# Main.net
KiCad netlist of a schematic drawn in Altium Designer
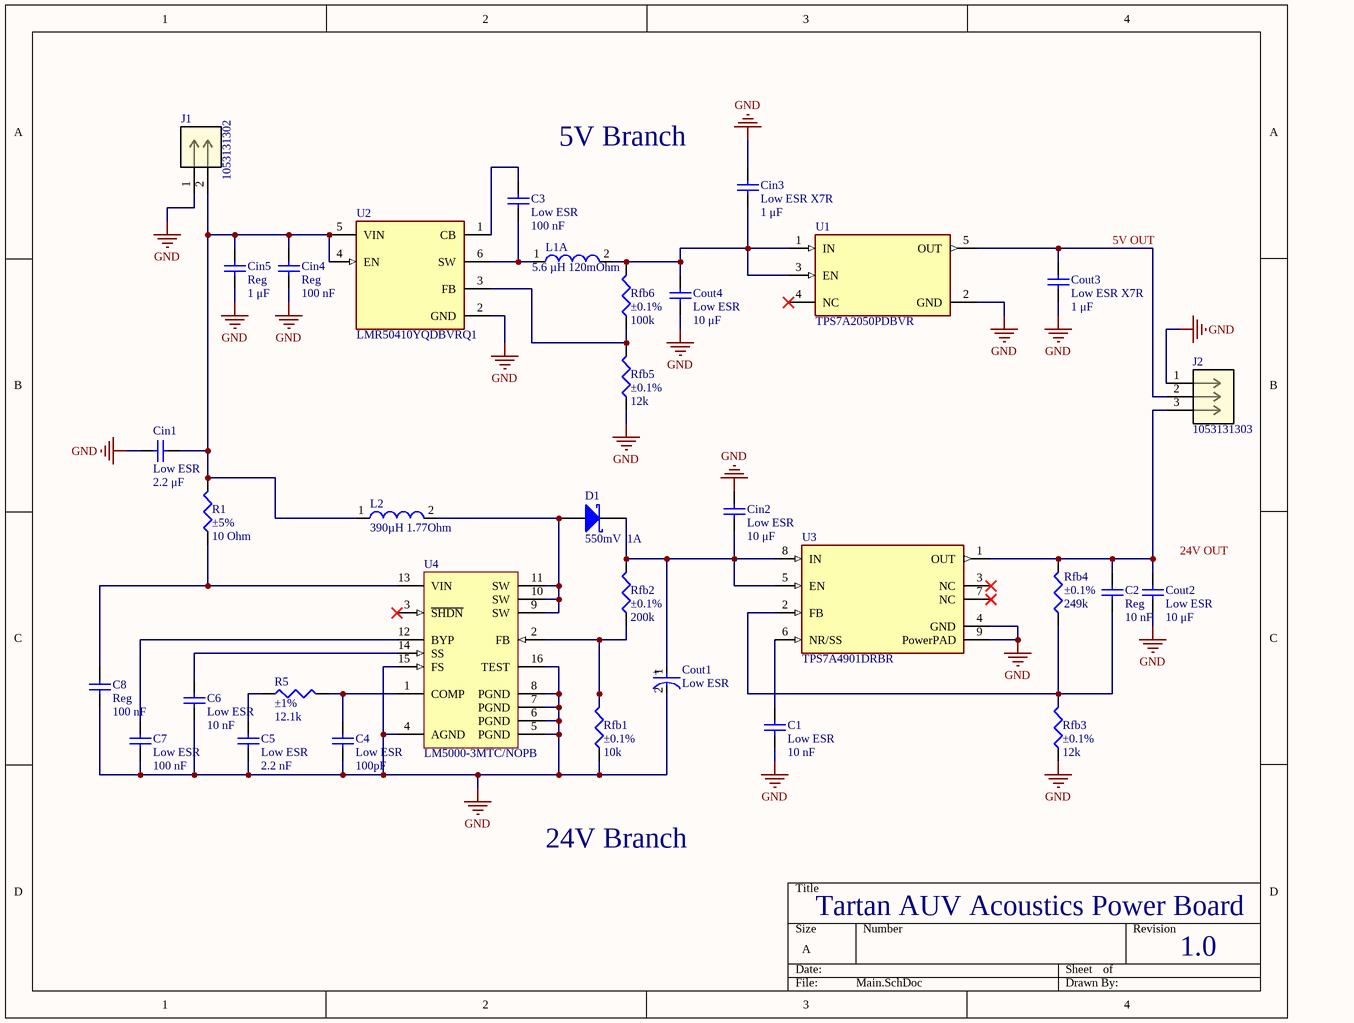
[diagram p0: Main.SchDoc]

(export (version "E")
  (design (tool "Eeschema 10.0.6"))
  (components
    (comp (ref "C1")
      (value "Low ESR")
      (footprint "C0805")
      (description "Capacitor")
      (fields (field (name "ALTIUM_VALUE") "10 nF") (field (name "PUBLISHER") "Altium Limited"))
      (libsource (lib "Miscellaneous Devices") (part "Cap"))
    )
    (comp (ref "C2")
      (value "Reg")
      (footprint "C0805")
      (description "Capacitor")
      (fields (field (name "ALTIUM_VALUE") "10 nF") (field (name "PUBLISHER") "Altium Limited"))
      (libsource (lib "Miscellaneous Devices") (part "Cap"))
    )
    (comp (ref "C3")
      (value "Low ESR")
      (footprint "C0805")
      (description "Capacitor")
      (fields (field (name "ALTIUM_VALUE") "100 nF") (field (name "PUBLISHER") "Altium Limited"))
      (libsource (lib "Miscellaneous Devices") (part "Cap"))
    )
    (comp (ref "C4")
      (value "Low ESR")
      (footprint "C0805")
      (description "Capacitor")
      (fields (field (name "ALTIUM_VALUE") "100pF") (field (name "PUBLISHER") "Altium Limited"))
      (libsource (lib "Miscellaneous Devices") (part "Cap"))
    )
    (comp (ref "C5")
      (value "Low ESR")
      (footprint "C0805")
      (description "Capacitor")
      (fields (field (name "ALTIUM_VALUE") "2.2 nF") (field (name "PUBLISHER") "Altium Limited"))
      (libsource (lib "Miscellaneous Devices") (part "Cap"))
    )
    (comp (ref "C6")
      (value "Low ESR")
      (footprint "C0805")
      (description "Capacitor")
      (fields (field (name "ALTIUM_VALUE") "10 nF") (field (name "PUBLISHER") "Altium Limited"))
      (libsource (lib "Miscellaneous Devices") (part "Cap"))
    )
    (comp (ref "C7")
      (value "Low ESR")
      (footprint "C0805")
      (description "Capacitor")
      (fields (field (name "ALTIUM_VALUE") "100 nF") (field (name "PUBLISHER") "Altium Limited"))
      (libsource (lib "Miscellaneous Devices") (part "Cap"))
    )
    (comp (ref "C8")
      (value "Reg")
      (footprint "C0805")
      (description "Capacitor")
      (fields (field (name "ALTIUM_VALUE") "100 nF") (field (name "PUBLISHER") "Altium Limited"))
      (libsource (lib "Miscellaneous Devices") (part "Cap"))
    )
    (comp (ref "Cin1")
      (value "Low ESR")
      (footprint "C0805")
      (description "Capacitor")
      (fields (field (name "ALTIUM_VALUE") "2.2 μF") (field (name "PUBLISHER") "Altium Limited"))
      (libsource (lib "Miscellaneous Devices") (part "Cap"))
    )
    (comp (ref "Cin2")
      (value "Low ESR")
      (footprint "C1210")
      (description "Capacitor")
      (fields (field (name "ALTIUM_VALUE") "10 μF") (field (name "PUBLISHER") "Altium Limited"))
      (libsource (lib "Miscellaneous Devices") (part "Cap"))
    )
    (comp (ref "Cin3")
      (value "Low ESR X7R")
      (footprint "C0805")
      (description "Capacitor")
      (fields (field (name "ALTIUM_VALUE") "1 μF") (field (name "PUBLISHER") "Altium Limited"))
      (libsource (lib "Miscellaneous Devices") (part "Cap"))
    )
    (comp (ref "Cin4")
      (value "Reg")
      (footprint "C0805")
      (description "Capacitor")
      (fields (field (name "ALTIUM_VALUE") "100 nF") (field (name "PUBLISHER") "Altium Limited"))
      (libsource (lib "Miscellaneous Devices") (part "Cap"))
    )
    (comp (ref "Cin5")
      (value "Reg")
      (footprint "C0805")
      (description "Capacitor")
      (fields (field (name "ALTIUM_VALUE") "1 μF") (field (name "PUBLISHER") "Altium Limited"))
      (libsource (lib "Miscellaneous Devices") (part "Cap"))
    )
    (comp (ref "Cout1")
      (value "Low ESR")
      (footprint "FP-EEH-D8-MFG")
      (description "Conductive Polymer Hybrid Aluminum Electrolytic Capacitors 68uF ±20% 35V RADIAL SMT 6.3x7.7mm")
      (fields (field (name "VOLTAGE") "35V") (field (name "TOLERANCE") "20%"))
      (libsource (lib "Altium Content Vault") (part "a00bbbee19879c290e62620ae7e47b1"))
    )
    (comp (ref "Cout2")
      (value "Low ESR")
      (footprint "C1210")
      (description "Capacitor")
      (fields (field (name "ALTIUM_VALUE") "10 μF") (field (name "PUBLISHER") "Altium Limited"))
      (libsource (lib "Miscellaneous Devices") (part "Cap"))
    )
    (comp (ref "Cout3")
      (value "Low ESR X7R")
      (footprint "C0805")
      (description "Capacitor")
      (fields (field (name "ALTIUM_VALUE") "1 μF") (field (name "PUBLISHER") "Altium Limited"))
      (libsource (lib "Miscellaneous Devices") (part "Cap"))
    )
    (comp (ref "Cout4")
      (value "Low ESR")
      (footprint "C1210")
      (description "Capacitor")
      (fields (field (name "ALTIUM_VALUE") "10 μF") (field (name "PUBLISHER") "Altium Limited"))
      (libsource (lib "Miscellaneous Devices") (part "Cap"))
    )
    (comp (ref "D1")
      (value "550mV  1A")
      (footprint "SMB")
      (description "Schottky Diode")
      (fields (field (name "PUBLISHER") "Altium Limited"))
      (libsource (lib "Miscellaneous Devices") (part "D Schottky"))
    )
    (comp (ref "J1")
      (value "1053131302")
      (footprint "CON_1053131302")
      (description "No Description Available")
      (fields (field (name "COPYRIGHT") "Copyright (C) 2022 Ultra Librarian. All rights reserved."))
      (libsource (lib "1053131302") (part "1053131302"))
    )
    (comp (ref "J2")
      (value "1053131303")
      (footprint "CON_1053131303")
      (description "No Description Available")
      (fields (field (name "COPYRIGHT") "Copyright (C) 2022 Ultra Librarian. All rights reserved."))
      (libsource (lib "1053131303") (part "1053131303"))
    )
    (comp (ref "L1")
      (value "5.6 µH 120mOhm")
      (footprint "WE-TPC-8012")
      (description "SMD Shielded Tiny Power Inductor WE-TPC, L = 5.60 µH")
      (libsource (lib "Altium Content Vault") (part "PAS-IND-INDUCTOR-4L"))
    )
    (comp (ref "L2")
      (value "390µH 1.77Ohm")
      (footprint "WE-PD2-L")
      (description "SMD Power Inductor WE-PD2, L = 390 µH")
      (libsource (lib "Altium Content Vault") (part "PAS-IND-INDUCTOR-2"))
    )
    (comp (ref "R1")
      (value "±5%")
      (footprint "J1-0603")
      (description "Resistor")
      (fields (field (name "ALTIUM_VALUE") "10 Ohm") (field (name "PUBLISHER") "Altium Limited"))
      (libsource (lib "Miscellaneous Devices") (part "Res3"))
    )
    (comp (ref "R5")
      (value "±1%")
      (footprint "J1-0603")
      (description "Resistor")
      (fields (field (name "ALTIUM_VALUE") "12.1k") (field (name "PUBLISHER") "Altium Limited"))
      (libsource (lib "Miscellaneous Devices") (part "Res3"))
    )
    (comp (ref "Rfb1")
      (value "±0.1%")
      (footprint "J1-0603")
      (description "Resistor")
      (fields (field (name "ALTIUM_VALUE") "10k") (field (name "PUBLISHER") "Altium Limited"))
      (libsource (lib "Miscellaneous Devices") (part "Res3"))
    )
    (comp (ref "Rfb2")
      (value "±0.1%")
      (footprint "J1-0603")
      (description "Resistor")
      (fields (field (name "ALTIUM_VALUE") "200k") (field (name "PUBLISHER") "Altium Limited"))
      (libsource (lib "Miscellaneous Devices") (part "Res3"))
    )
    (comp (ref "Rfb3")
      (value "±0.1%")
      (footprint "J1-0603")
      (description "Resistor")
      (fields (field (name "ALTIUM_VALUE") "12k") (field (name "PUBLISHER") "Altium Limited"))
      (libsource (lib "Miscellaneous Devices") (part "Res3"))
    )
    (comp (ref "Rfb4")
      (value "±0.1%")
      (footprint "J1-0603")
      (description "Resistor")
      (fields (field (name "ALTIUM_VALUE") "249k") (field (name "PUBLISHER") "Altium Limited"))
      (libsource (lib "Miscellaneous Devices") (part "Res3"))
    )
    (comp (ref "Rfb5")
      (value "±0.1%")
      (footprint "J1-0603")
      (description "Resistor")
      (fields (field (name "ALTIUM_VALUE") "12k") (field (name "PUBLISHER") "Altium Limited"))
      (libsource (lib "Miscellaneous Devices") (part "Res3"))
    )
    (comp (ref "Rfb6")
      (value "±0.1%")
      (footprint "J1-0603")
      (description "Resistor")
      (fields (field (name "ALTIUM_VALUE") "100k") (field (name "PUBLISHER") "Altium Limited"))
      (libsource (lib "Miscellaneous Devices") (part "Res3"))
    )
    (comp (ref "U1")
      (value "TPS7A2050PDBVR")
      (footprint "FP-DBV0005A-IPC_B")
      (libsource (lib "Altium Content Vault") (part "016a98dcc07c0606c38eea974f4970a"))
    )
    (comp (ref "U2")
      (value "LMR50410YQDBVRQ1")
      (footprint "FP-DBV0006A-MFG")
      (description "NIXON PLUS-LMR50410YQDBVRQ1")
      (libsource (lib "Altium Content Vault") (part "dd20875c80c3702360114ef84ecc10b"))
    )
    (comp (ref "U3")
      (value "TPS7A4901DRBR")
      (footprint "FP-DRB0008A-MFG")
      (description "None")
      (libsource (lib "Altium Content Vault") (part "ef16affa275921b576f8415521af00b"))
    )
    (comp (ref "U4")
      (value "LM5000-3MTC/NOPB")
      (footprint "PW0016A_L")
      (description "High Voltage Switch Mode Regulator, 16-pin TSSOP, Pb-Free")
      (fields (field (name "MANUFACTURER") "Texas Instruments"))
      (libsource (lib "Altium Content Vault") (part "PM-SMPS-LM5000-16"))
    )
  )
  (nets
    (net (code "1") (name "GND") (class "Default")
      (node (ref "C1") (pin "1") (pinfunction "1_1") (pintype "passive"))
      (node (ref "C4") (pin "1") (pinfunction "1_1") (pintype "passive"))
      (node (ref "C5") (pin "1") (pinfunction "1_1") (pintype "passive"))
      (node (ref "C6") (pin "1") (pinfunction "1_1") (pintype "passive"))
      (node (ref "C7") (pin "1") (pinfunction "1_1") (pintype "passive"))
      (node (ref "C8") (pin "1") (pinfunction "1_1") (pintype "passive"))
      (node (ref "Cin1") (pin "1") (pinfunction "1_1") (pintype "passive"))
      (node (ref "Cin2") (pin "2") (pinfunction "2_2") (pintype "passive"))
      (node (ref "Cin3") (pin "2") (pinfunction "2_2") (pintype "passive"))
      (node (ref "Cin4") (pin "1") (pinfunction "1_1") (pintype "passive"))
      (node (ref "Cin5") (pin "1") (pinfunction "1_1") (pintype "passive"))
      (node (ref "Cout1") (pin "2") (pinfunction "A_2") (pintype "passive"))
      (node (ref "Cout2") (pin "1") (pinfunction "1_1") (pintype "passive"))
      (node (ref "Cout3") (pin "1") (pinfunction "1_1") (pintype "passive"))
      (node (ref "Cout4") (pin "1") (pinfunction "1_1") (pintype "passive"))
      (node (ref "J1") (pin "1") (pinfunction "1_1") (pintype "passive"))
      (node (ref "J2") (pin "1") (pinfunction "1_1") (pintype "passive"))
      (node (ref "Rfb1") (pin "1") (pinfunction "1_1") (pintype "passive"))
      (node (ref "Rfb3") (pin "1") (pinfunction "1_1") (pintype "passive"))
      (node (ref "Rfb5") (pin "1") (pinfunction "1_1") (pintype "passive"))
      (node (ref "U1") (pin "2") (pinfunction "GND_2") (pintype "power_in"))
      (node (ref "U2") (pin "2") (pinfunction "GND_2") (pintype "power_in"))
      (node (ref "U3") (pin "4") (pinfunction "GND_4") (pintype "power_in"))
      (node (ref "U3") (pin "9") (pinfunction "PowerPAD_9") (pintype "power_in"))
      (node (ref "U4") (pin "15") (pinfunction "FS_15") (pintype "input"))
      (node (ref "U4") (pin "16") (pinfunction "TEST_16") (pintype "passive"))
      (node (ref "U4") (pin "4") (pinfunction "AGND_4") (pintype "power_in"))
      (node (ref "U4") (pin "5") (pinfunction "PGND_5") (pintype "power_in"))
      (node (ref "U4") (pin "6") (pinfunction "PGND_6") (pintype "power_in"))
      (node (ref "U4") (pin "7") (pinfunction "PGND_7") (pintype "power_in"))
      (node (ref "U4") (pin "8") (pinfunction "PGND_8") (pintype "power_in"))
    )
    (net (code "2") (name "Net-(C5-Pad2)") (class "Default")
      (node (ref "C5") (pin "2") (pinfunction "2_2") (pintype "passive"))
      (node (ref "R5") (pin "1") (pinfunction "1_1") (pintype "passive"))
    )
    (net (code "3") (name "Net-(Cout1-C)") (class "Default")
      (node (ref "Cin2") (pin "1") (pinfunction "1_1") (pintype "passive"))
      (node (ref "Cout1") (pin "1") (pinfunction "C_1") (pintype "passive"))
      (node (ref "D1") (pin "2") (pinfunction "K_2") (pintype "passive"))
      (node (ref "Rfb2") (pin "2") (pinfunction "2_2") (pintype "passive"))
      (node (ref "U3") (pin "5") (pinfunction "EN_5") (pintype "input"))
      (node (ref "U3") (pin "8") (pinfunction "IN_8") (pintype "input"))
    )
    (net (code "4") (name "Net-(D1-A)") (class "Default")
      (node (ref "D1") (pin "1") (pinfunction "A_1") (pintype "passive"))
      (node (ref "L2") (pin "2") (pinfunction "2_2") (pintype "passive"))
      (node (ref "U4") (pin "10") (pinfunction "SW_10") (pintype "power_in"))
      (node (ref "U4") (pin "11") (pinfunction "SW_11") (pintype "power_in"))
      (node (ref "U4") (pin "9") (pinfunction "SW_9") (pintype "power_in"))
    )
    (net (code "5") (name "Net-(U1-EN)") (class "Default")
      (node (ref "Cin3") (pin "1") (pinfunction "1_1") (pintype "passive"))
      (node (ref "Cout4") (pin "2") (pinfunction "2_2") (pintype "passive"))
      (node (ref "L1") (pin "2") (pinfunction "2_2") (pintype "passive"))
      (node (ref "Rfb6") (pin "2") (pinfunction "2_2") (pintype "passive"))
      (node (ref "U1") (pin "1") (pinfunction "IN_1") (pintype "input"))
      (node (ref "U1") (pin "3") (pinfunction "EN_3") (pintype "input"))
    )
    (net (code "6") (name "Net-(U1-OUT)") (class "Default")
      (node (ref "Cout3") (pin "2") (pinfunction "2_2") (pintype "passive"))
      (node (ref "J2") (pin "2") (pinfunction "2_2") (pintype "passive"))
      (node (ref "U1") (pin "5") (pinfunction "OUT_5") (pintype "output"))
    )
    (net (code "7") (name "Net-(U2-CB)") (class "Default")
      (node (ref "C3") (pin "2") (pinfunction "2_2") (pintype "passive"))
      (node (ref "U2") (pin "1") (pinfunction "CB_1") (pintype "passive"))
    )
    (net (code "8") (name "Net-(U2-EN)") (class "Default")
      (node (ref "Cin1") (pin "2") (pinfunction "2_2") (pintype "passive"))
      (node (ref "Cin4") (pin "2") (pinfunction "2_2") (pintype "passive"))
      (node (ref "Cin5") (pin "2") (pinfunction "2_2") (pintype "passive"))
      (node (ref "J1") (pin "2") (pinfunction "2_2") (pintype "passive"))
      (node (ref "L2") (pin "1") (pinfunction "1_1") (pintype "passive"))
      (node (ref "R1") (pin "2") (pinfunction "2_2") (pintype "passive"))
      (node (ref "U2") (pin "4") (pinfunction "EN_4") (pintype "input"))
      (node (ref "U2") (pin "5") (pinfunction "VIN_5") (pintype "power_in"))
    )
    (net (code "9") (name "Net-(U2-FB)") (class "Default")
      (node (ref "Rfb5") (pin "2") (pinfunction "2_2") (pintype "passive"))
      (node (ref "Rfb6") (pin "1") (pinfunction "1_1") (pintype "passive"))
      (node (ref "U2") (pin "3") (pinfunction "FB_3") (pintype "passive"))
    )
    (net (code "10") (name "Net-(U2-SW)") (class "Default")
      (node (ref "C3") (pin "1") (pinfunction "1_1") (pintype "passive"))
      (node (ref "L1") (pin "1") (pinfunction "1_1") (pintype "passive"))
      (node (ref "U2") (pin "6") (pinfunction "SW_6") (pintype "power_in"))
    )
    (net (code "11") (name "Net-(U3-FB)") (class "Default")
      (node (ref "C2") (pin "1") (pinfunction "1_1") (pintype "passive"))
      (node (ref "Rfb3") (pin "2") (pinfunction "2_2") (pintype "passive"))
      (node (ref "Rfb4") (pin "1") (pinfunction "1_1") (pintype "passive"))
      (node (ref "U3") (pin "2") (pinfunction "FB_2") (pintype "input"))
    )
    (net (code "12") (name "Net-(U3-NR{slash}SS)") (class "Default")
      (node (ref "C1") (pin "2") (pinfunction "2_2") (pintype "passive"))
      (node (ref "U3") (pin "6") (pinfunction "NR/SS_6") (pintype "input"))
    )
    (net (code "13") (name "Net-(U3-OUT)") (class "Default")
      (node (ref "C2") (pin "2") (pinfunction "2_2") (pintype "passive"))
      (node (ref "Cout2") (pin "2") (pinfunction "2_2") (pintype "passive"))
      (node (ref "J2") (pin "3") (pinfunction "3_3") (pintype "passive"))
      (node (ref "Rfb4") (pin "2") (pinfunction "2_2") (pintype "passive"))
      (node (ref "U3") (pin "1") (pinfunction "OUT_1") (pintype "output"))
    )
    (net (code "14") (name "Net-(U4-BYP)") (class "Default")
      (node (ref "C7") (pin "2") (pinfunction "2_2") (pintype "passive"))
      (node (ref "U4") (pin "12") (pinfunction "BYP_12") (pintype "passive"))
    )
    (net (code "15") (name "Net-(U4-COMP)") (class "Default")
      (node (ref "C4") (pin "2") (pinfunction "2_2") (pintype "passive"))
      (node (ref "R5") (pin "2") (pinfunction "2_2") (pintype "passive"))
      (node (ref "U4") (pin "1") (pinfunction "COMP_1") (pintype "passive"))
    )
    (net (code "16") (name "Net-(U4-FB)") (class "Default")
      (node (ref "Rfb1") (pin "2") (pinfunction "2_2") (pintype "passive"))
      (node (ref "Rfb2") (pin "1") (pinfunction "1_1") (pintype "passive"))
      (node (ref "U4") (pin "2") (pinfunction "FB_2") (pintype "input"))
    )
    (net (code "17") (name "Net-(U4-SS)") (class "Default")
      (node (ref "C6") (pin "2") (pinfunction "2_2") (pintype "passive"))
      (node (ref "U4") (pin "14") (pinfunction "SS_14") (pintype "input"))
    )
    (net (code "18") (name "Net-(U4-VIN)") (class "Default")
      (node (ref "C8") (pin "2") (pinfunction "2_2") (pintype "passive"))
      (node (ref "R1") (pin "1") (pinfunction "1_1") (pintype "passive"))
      (node (ref "U4") (pin "13") (pinfunction "VIN_13") (pintype "power_in"))
    )
    (net (code "19") (name "unconnected-(U1-NC-Pad4)") (class "Default")
      (node (ref "U1") (pin "4") (pinfunction "NC_4") (pintype "passive+no_connect"))
    )
    (net (code "20") (name "unconnected-(U3-NC-Pad3)") (class "Default")
      (node (ref "U3") (pin "3") (pinfunction "NC_3") (pintype "passive+no_connect"))
    )
    (net (code "21") (name "unconnected-(U3-NC-Pad7)") (class "Default")
      (node (ref "U3") (pin "7") (pinfunction "NC_7") (pintype "passive+no_connect"))
    )
    (net (code "22") (name "unconnected-(U4-~{SHDN}-Pad3)") (class "Default")
      (node (ref "U4") (pin "3") (pinfunction "~{SHDN}_3") (pintype "input+no_connect"))
    )
  )
)
